# RG_Medium_Matrix.net
KiCad netlist of a schematic drawn in EAGLE
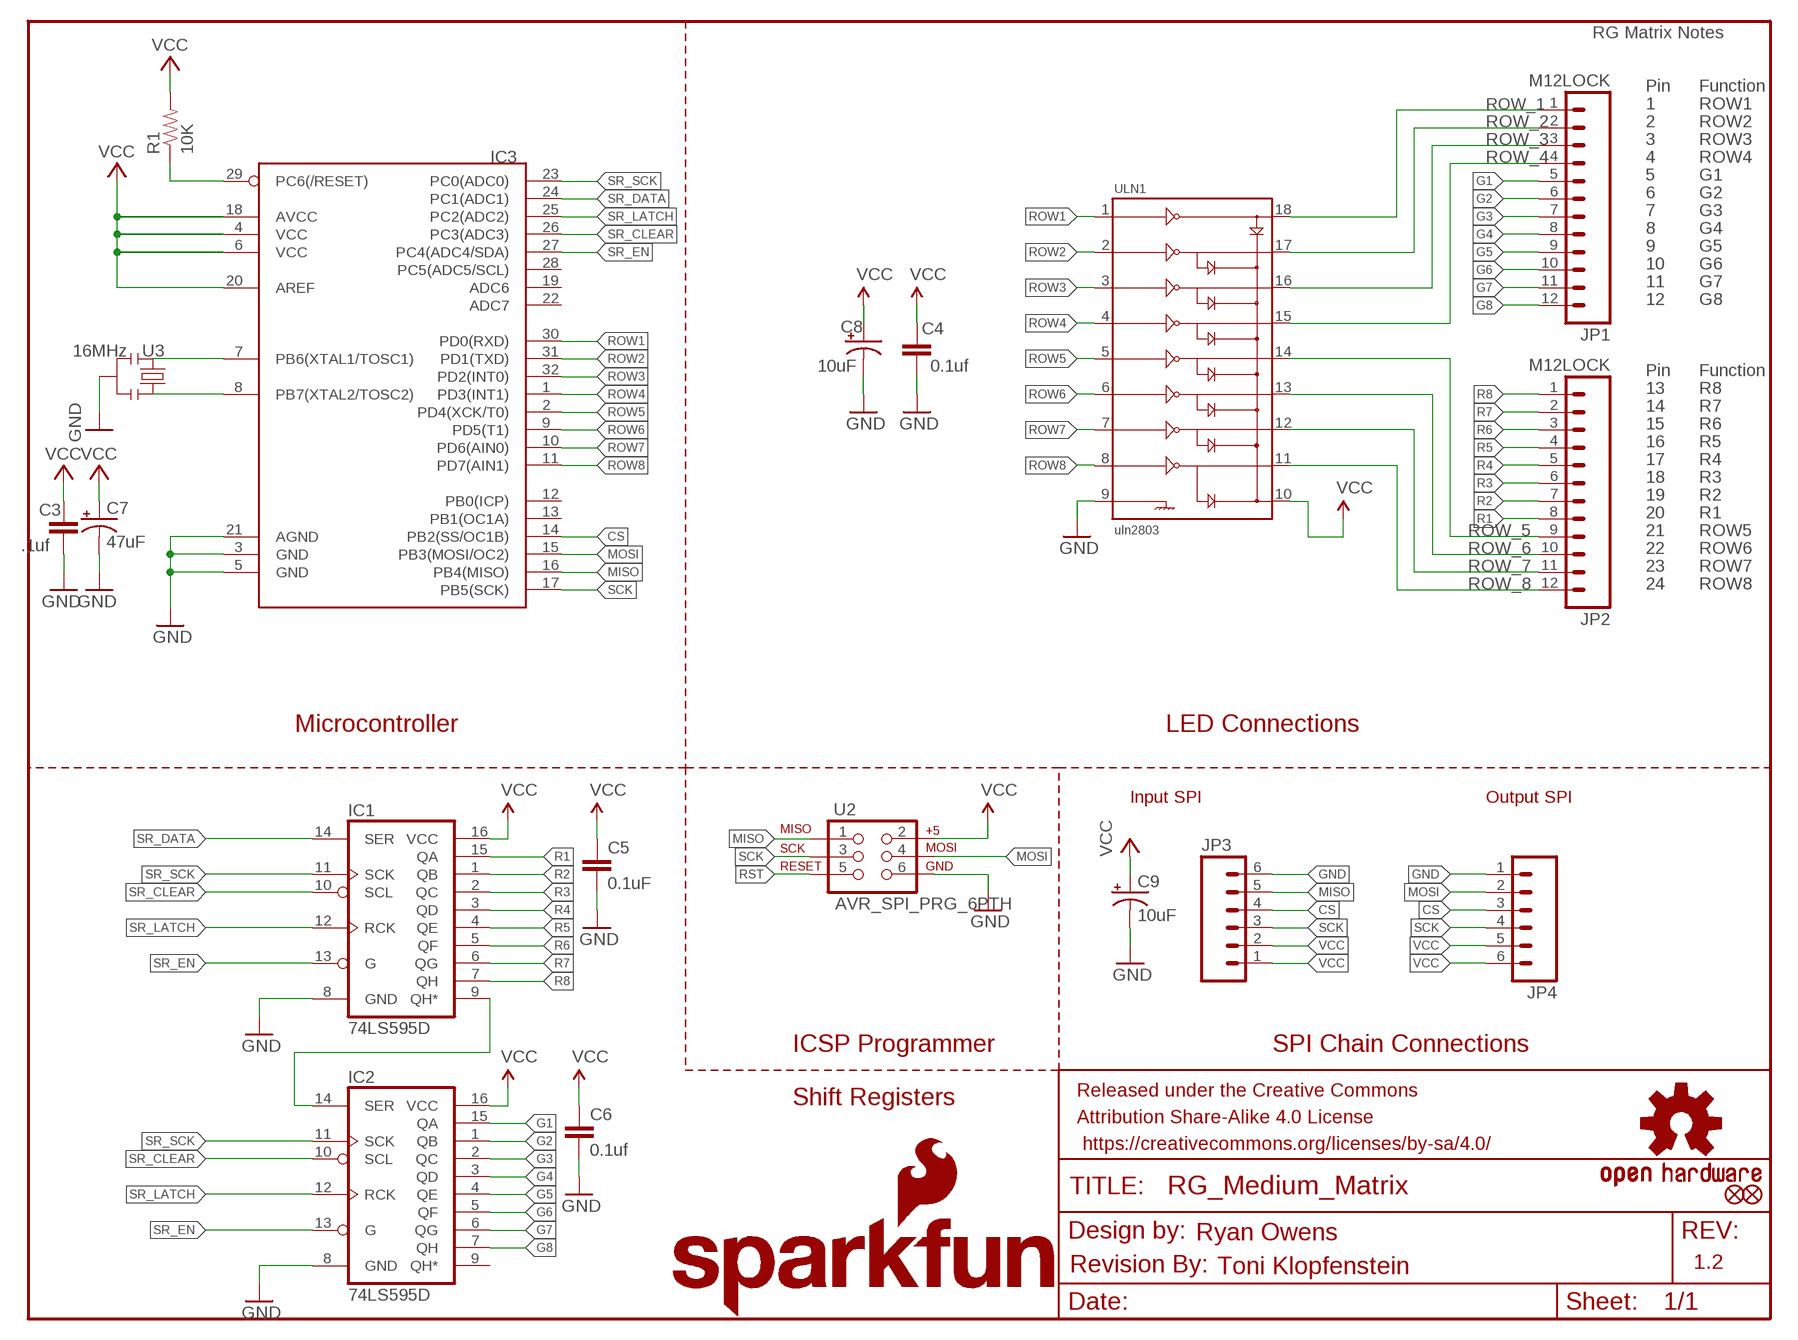
[diagram p0: schematic, sheet 1]

(export (version "E")
  (design (tool "Eeschema 10.0.6"))
  (components
    (comp (ref "C3")
      (value ".1uf")
      (footprint "eagle-import:0603-CAP")
      (libsource (lib "eagle-import") (part "0.1UF-25V(+80/-20%)(0603)"))
    )
    (comp (ref "C4")
      (value "0.1uf")
      (footprint "eagle-import:0603-CAP")
      (libsource (lib "eagle-import") (part "0.1UF-25V(+80/-20%)(0603)"))
    )
    (comp (ref "C5")
      (value "0.1uF")
      (footprint "eagle-import:0603-CAP")
      (libsource (lib "eagle-import") (part "0.1UF-25V(+80/-20%)(0603)"))
    )
    (comp (ref "C6")
      (value "0.1uf")
      (footprint "eagle-import:0603-CAP")
      (libsource (lib "eagle-import") (part "0.1UF-25V(+80/-20%)(0603)"))
    )
    (comp (ref "C7")
      (value "47uF")
      (footprint "eagle-import:EIA3528")
      (libsource (lib "eagle-import") (part "CAP_POL3528"))
    )
    (comp (ref "C8")
      (value "10uF")
      (footprint "eagle-import:EIA3216")
      (libsource (lib "eagle-import") (part "CAP_POL1206"))
    )
    (comp (ref "C9")
      (value "10uF")
      (footprint "eagle-import:EIA3216")
      (libsource (lib "eagle-import") (part "CAP_POL1206"))
    )
    (comp (ref "FRAME1")
      (value "FRAME-LETTER")
      (footprint "eagle-import:CREATIVE_COMMONS")
      (libsource (lib "eagle-import") (part "FRAME-LETTER"))
    )
    (comp (ref "IC1")
      (value "74LS595D")
      (footprint "eagle-import:SO16")
      (libsource (lib "eagle-import") (part "74595DLS"))
    )
    (comp (ref "IC2")
      (value "74LS595D")
      (footprint "eagle-import:SO16")
      (libsource (lib "eagle-import") (part "74595DLS"))
    )
    (comp (ref "IC3")
      (value "ATMEGA328_SMT")
      (footprint "eagle-import:TQFP32-08")
      (libsource (lib "eagle-import") (part "ATMEGA328_SMT"))
    )
    (comp (ref "JP1")
      (value "M12LOCK")
      (footprint "eagle-import:1X12_LOCK")
      (libsource (lib "eagle-import") (part "M12LOCK"))
    )
    (comp (ref "JP2")
      (value "M12LOCK")
      (footprint "eagle-import:1X12_LOCK")
      (libsource (lib "eagle-import") (part "M12LOCK"))
    )
    (comp (ref "JP3")
      (value "M06LOCK")
      (footprint "eagle-import:1X06_LOCK")
      (libsource (lib "eagle-import") (part "M06LOCK"))
    )
    (comp (ref "JP4")
      (value "M06LOCK")
      (footprint "eagle-import:1X06_LOCK")
      (libsource (lib "eagle-import") (part "M06LOCK"))
    )
    (comp (ref "LOGO1")
      (value "OSHW-LOGOS")
      (footprint "eagle-import:OSHW-LOGO-S")
      (libsource (lib "eagle-import") (part "OSHW-LOGOS"))
    )
    (comp (ref "LOGO2")
      (value "SFE_LOGO_NAME_FLAME.1_INCH")
      (footprint "eagle-import:SFE_LOGO_NAME_FLAME_.1")
      (libsource (lib "eagle-import") (part "SFE_LOGO_NAME_FLAME.1_INCH"))
    )
    (comp (ref "R1")
      (value "10K")
      (footprint "eagle-import:0603-RES")
      (libsource (lib "eagle-import") (part "10KOHM1/10W1%(0603)0603"))
    )
    (comp (ref "U$1")
      (value "FIDUCIAL1X2")
      (footprint "eagle-import:FIDUCIAL-1X2")
      (libsource (lib "eagle-import") (part "FIDUCIAL1X2"))
    )
    (comp (ref "U$2")
      (value "REVISION")
      (footprint "eagle-import:REVISION")
      (libsource (lib "eagle-import") (part "REVISION"))
    )
    (comp (ref "U$3")
      (value "FIDUCIAL1X2")
      (footprint "eagle-import:FIDUCIAL-1X2")
      (libsource (lib "eagle-import") (part "FIDUCIAL1X2"))
    )
    (comp (ref "U2")
      (value "AVR_SPI_PRG_6PTH")
      (footprint "eagle-import:2X3")
      (libsource (lib "eagle-import") (part "AVR_SPI_PRG_6PTH"))
    )
    (comp (ref "U3")
      (value "16MHz")
      (footprint "eagle-import:RESONATOR-SMD")
      (libsource (lib "eagle-import") (part "RESONATORSMD"))
    )
    (comp (ref "ULN1")
      (value "uln2803")
      (footprint "eagle-import:SO18L")
      (libsource (lib "eagle-import") (part "ULN2803SOICW"))
    )
  )
  (nets
    (net (code "1") (name "/ROW_1") (class "Default")
      (node (ref "JP1") (pin "1") (pinfunction "1_1") (pintype "passive"))
      (node (ref "ULN1") (pin "18") (pinfunction "18_18") (pintype "bidirectional"))
    )
    (net (code "2") (name "/ROW_2") (class "Default")
      (node (ref "JP1") (pin "2") (pinfunction "2_2") (pintype "passive"))
      (node (ref "ULN1") (pin "17") (pinfunction "17_17") (pintype "bidirectional"))
    )
    (net (code "3") (name "/ROW_3") (class "Default")
      (node (ref "JP1") (pin "3") (pinfunction "3_3") (pintype "passive"))
      (node (ref "ULN1") (pin "16") (pinfunction "16_16") (pintype "bidirectional"))
    )
    (net (code "4") (name "/ROW_4") (class "Default")
      (node (ref "JP1") (pin "4") (pinfunction "4_4") (pintype "passive"))
      (node (ref "ULN1") (pin "15") (pinfunction "15_15") (pintype "bidirectional"))
    )
    (net (code "5") (name "/ROW_5") (class "Default")
      (node (ref "JP2") (pin "9") (pinfunction "9_9") (pintype "passive"))
      (node (ref "ULN1") (pin "14") (pinfunction "14_14") (pintype "bidirectional"))
    )
    (net (code "6") (name "/ROW_6") (class "Default")
      (node (ref "JP2") (pin "10") (pinfunction "10_10") (pintype "passive"))
      (node (ref "ULN1") (pin "13") (pinfunction "13_13") (pintype "bidirectional"))
    )
    (net (code "7") (name "/ROW_7") (class "Default")
      (node (ref "JP2") (pin "11") (pinfunction "11_11") (pintype "passive"))
      (node (ref "ULN1") (pin "12") (pinfunction "12_12") (pintype "bidirectional"))
    )
    (net (code "8") (name "/ROW_8") (class "Default")
      (node (ref "JP2") (pin "12") (pinfunction "12_12") (pintype "passive"))
      (node (ref "ULN1") (pin "11") (pinfunction "11_11") (pintype "bidirectional"))
    )
    (net (code "9") (name "CS") (class "Default")
      (node (ref "IC3") (pin "14") (pinfunction "PB2(SS/OC1B)_14") (pintype "bidirectional"))
      (node (ref "JP3") (pin "4") (pinfunction "4_4") (pintype "passive"))
      (node (ref "JP4") (pin "3") (pinfunction "3_3") (pintype "passive"))
    )
    (net (code "10") (name "G1") (class "Default")
      (node (ref "IC2") (pin "15") (pinfunction "QA_15") (pintype "tri_state"))
      (node (ref "JP1") (pin "5") (pinfunction "5_5") (pintype "passive"))
    )
    (net (code "11") (name "G2") (class "Default")
      (node (ref "IC2") (pin "1") (pinfunction "QB_1") (pintype "tri_state"))
      (node (ref "JP1") (pin "6") (pinfunction "6_6") (pintype "passive"))
    )
    (net (code "12") (name "G3") (class "Default")
      (node (ref "IC2") (pin "2") (pinfunction "QC_2") (pintype "tri_state"))
      (node (ref "JP1") (pin "7") (pinfunction "7_7") (pintype "passive"))
    )
    (net (code "13") (name "G4") (class "Default")
      (node (ref "IC2") (pin "3") (pinfunction "QD_3") (pintype "tri_state"))
      (node (ref "JP1") (pin "8") (pinfunction "8_8") (pintype "passive"))
    )
    (net (code "14") (name "G5") (class "Default")
      (node (ref "IC2") (pin "4") (pinfunction "QE_4") (pintype "tri_state"))
      (node (ref "JP1") (pin "9") (pinfunction "9_9") (pintype "passive"))
    )
    (net (code "15") (name "G6") (class "Default")
      (node (ref "IC2") (pin "5") (pinfunction "QF_5") (pintype "tri_state"))
      (node (ref "JP1") (pin "10") (pinfunction "10_10") (pintype "passive"))
    )
    (net (code "16") (name "G7") (class "Default")
      (node (ref "IC2") (pin "6") (pinfunction "QG_6") (pintype "tri_state"))
      (node (ref "JP1") (pin "11") (pinfunction "11_11") (pintype "passive"))
    )
    (net (code "17") (name "G8") (class "Default")
      (node (ref "IC2") (pin "7") (pinfunction "QH_7") (pintype "tri_state"))
      (node (ref "JP1") (pin "12") (pinfunction "12_12") (pintype "passive"))
    )
    (net (code "18") (name "GND") (class "Default")
      (node (ref "C3") (pin "2") (pinfunction "2_2") (pintype "passive"))
      (node (ref "C4") (pin "1") (pinfunction "1_1") (pintype "passive"))
      (node (ref "C5") (pin "2") (pinfunction "2_2") (pintype "passive"))
      (node (ref "C6") (pin "2") (pinfunction "2_2") (pintype "passive"))
      (node (ref "C7") (pin "C") (pinfunction "-_C") (pintype "passive"))
      (node (ref "C8") (pin "C") (pinfunction "-_C") (pintype "passive"))
      (node (ref "C9") (pin "C") (pinfunction "-_C") (pintype "passive"))
      (node (ref "IC1") (pin "8") (pinfunction "GND_8") (pintype "power_in"))
      (node (ref "IC2") (pin "8") (pinfunction "GND_8") (pintype "power_in"))
      (node (ref "IC3") (pin "21") (pinfunction "AGND_21") (pintype "bidirectional"))
      (node (ref "IC3") (pin "3") (pinfunction "GND_3") (pintype "bidirectional"))
      (node (ref "IC3") (pin "5") (pinfunction "GND_5") (pintype "bidirectional"))
      (node (ref "JP3") (pin "6") (pinfunction "6_6") (pintype "passive"))
      (node (ref "JP4") (pin "1") (pinfunction "1_1") (pintype "passive"))
      (node (ref "U2") (pin "6") (pinfunction "6_6") (pintype "passive"))
      (node (ref "U3") (pin "2") (pinfunction "2_2") (pintype "passive"))
      (node (ref "ULN1") (pin "9") (pinfunction "9_9") (pintype "bidirectional"))
    )
    (net (code "19") (name "MISO") (class "Default")
      (node (ref "IC3") (pin "16") (pinfunction "PB4(MISO)_16") (pintype "bidirectional"))
      (node (ref "JP3") (pin "5") (pinfunction "5_5") (pintype "passive"))
      (node (ref "U2") (pin "1") (pinfunction "1_1") (pintype "passive"))
    )
    (net (code "20") (name "MOSI") (class "Default")
      (node (ref "IC3") (pin "15") (pinfunction "PB3(MOSI/OC2)_15") (pintype "bidirectional"))
      (node (ref "JP4") (pin "2") (pinfunction "2_2") (pintype "passive"))
      (node (ref "U2") (pin "4") (pinfunction "4_4") (pintype "passive"))
    )
    (net (code "21") (name "Net-(IC1-QH*)") (class "Default")
      (node (ref "IC1") (pin "9") (pinfunction "QH*_9") (pintype "tri_state"))
      (node (ref "IC2") (pin "14") (pinfunction "SER_14") (pintype "input"))
    )
    (net (code "22") (name "Net-(IC3-PB6(XTAL1{slash}TOSC1))") (class "Default")
      (node (ref "IC3") (pin "7") (pinfunction "PB6(XTAL1/TOSC1)_7") (pintype "bidirectional"))
      (node (ref "U3") (pin "1") (pinfunction "1_1") (pintype "passive"))
    )
    (net (code "23") (name "Net-(IC3-PB7(XTAL2{slash}TOSC2))") (class "Default")
      (node (ref "IC3") (pin "8") (pinfunction "PB7(XTAL2/TOSC2)_8") (pintype "bidirectional"))
      (node (ref "U3") (pin "3") (pinfunction "3_3") (pintype "passive"))
    )
    (net (code "24") (name "R1") (class "Default")
      (node (ref "IC1") (pin "15") (pinfunction "QA_15") (pintype "tri_state"))
      (node (ref "JP2") (pin "8") (pinfunction "8_8") (pintype "passive"))
    )
    (net (code "25") (name "R2") (class "Default")
      (node (ref "IC1") (pin "1") (pinfunction "QB_1") (pintype "tri_state"))
      (node (ref "JP2") (pin "7") (pinfunction "7_7") (pintype "passive"))
    )
    (net (code "26") (name "R3") (class "Default")
      (node (ref "IC1") (pin "2") (pinfunction "QC_2") (pintype "tri_state"))
      (node (ref "JP2") (pin "6") (pinfunction "6_6") (pintype "passive"))
    )
    (net (code "27") (name "R4") (class "Default")
      (node (ref "IC1") (pin "3") (pinfunction "QD_3") (pintype "tri_state"))
      (node (ref "JP2") (pin "5") (pinfunction "5_5") (pintype "passive"))
    )
    (net (code "28") (name "R5") (class "Default")
      (node (ref "IC1") (pin "4") (pinfunction "QE_4") (pintype "tri_state"))
      (node (ref "JP2") (pin "4") (pinfunction "4_4") (pintype "passive"))
    )
    (net (code "29") (name "R6") (class "Default")
      (node (ref "IC1") (pin "5") (pinfunction "QF_5") (pintype "tri_state"))
      (node (ref "JP2") (pin "3") (pinfunction "3_3") (pintype "passive"))
    )
    (net (code "30") (name "R7") (class "Default")
      (node (ref "IC1") (pin "6") (pinfunction "QG_6") (pintype "tri_state"))
      (node (ref "JP2") (pin "2") (pinfunction "2_2") (pintype "passive"))
    )
    (net (code "31") (name "R8") (class "Default")
      (node (ref "IC1") (pin "7") (pinfunction "QH_7") (pintype "tri_state"))
      (node (ref "JP2") (pin "1") (pinfunction "1_1") (pintype "passive"))
    )
    (net (code "32") (name "ROW1") (class "Default")
      (node (ref "IC3") (pin "30") (pinfunction "PD0(RXD)_30") (pintype "bidirectional"))
      (node (ref "ULN1") (pin "1") (pinfunction "1_1") (pintype "bidirectional"))
    )
    (net (code "33") (name "ROW2") (class "Default")
      (node (ref "IC3") (pin "31") (pinfunction "PD1(TXD)_31") (pintype "bidirectional"))
      (node (ref "ULN1") (pin "2") (pinfunction "2_2") (pintype "bidirectional"))
    )
    (net (code "34") (name "ROW3") (class "Default")
      (node (ref "IC3") (pin "32") (pinfunction "PD2(INT0)_32") (pintype "bidirectional"))
      (node (ref "ULN1") (pin "3") (pinfunction "3_3") (pintype "bidirectional"))
    )
    (net (code "35") (name "ROW4") (class "Default")
      (node (ref "IC3") (pin "1") (pinfunction "PD3(INT1)_1") (pintype "bidirectional"))
      (node (ref "ULN1") (pin "4") (pinfunction "4_4") (pintype "bidirectional"))
    )
    (net (code "36") (name "ROW5") (class "Default")
      (node (ref "IC3") (pin "2") (pinfunction "PD4(XCK/T0)_2") (pintype "bidirectional"))
      (node (ref "ULN1") (pin "5") (pinfunction "5_5") (pintype "bidirectional"))
    )
    (net (code "37") (name "ROW6") (class "Default")
      (node (ref "IC3") (pin "9") (pinfunction "PD5(T1)_9") (pintype "bidirectional"))
      (node (ref "ULN1") (pin "6") (pinfunction "6_6") (pintype "bidirectional"))
    )
    (net (code "38") (name "ROW7") (class "Default")
      (node (ref "IC3") (pin "10") (pinfunction "PD6(AIN0)_10") (pintype "bidirectional"))
      (node (ref "ULN1") (pin "7") (pinfunction "7_7") (pintype "bidirectional"))
    )
    (net (code "39") (name "ROW8") (class "Default")
      (node (ref "IC3") (pin "11") (pinfunction "PD7(AIN1)_11") (pintype "bidirectional"))
      (node (ref "ULN1") (pin "8") (pinfunction "8_8") (pintype "bidirectional"))
    )
    (net (code "40") (name "RST") (class "Default")
      (node (ref "IC3") (pin "29") (pinfunction "PC6(/RESET)_29") (pintype "bidirectional"))
      (node (ref "R1") (pin "1") (pinfunction "1_1") (pintype "passive"))
      (node (ref "U2") (pin "5") (pinfunction "5_5") (pintype "passive"))
    )
    (net (code "41") (name "SCK") (class "Default")
      (node (ref "IC3") (pin "17") (pinfunction "PB5(SCK)_17") (pintype "bidirectional"))
      (node (ref "JP3") (pin "3") (pinfunction "3_3") (pintype "passive"))
      (node (ref "JP4") (pin "4") (pinfunction "4_4") (pintype "passive"))
      (node (ref "U2") (pin "3") (pinfunction "3_3") (pintype "passive"))
    )
    (net (code "42") (name "SR_CLEAR") (class "Default")
      (node (ref "IC1") (pin "10") (pinfunction "SCL_10") (pintype "input"))
      (node (ref "IC2") (pin "10") (pinfunction "SCL_10") (pintype "input"))
      (node (ref "IC3") (pin "26") (pinfunction "PC3(ADC3)_26") (pintype "bidirectional"))
    )
    (net (code "43") (name "SR_DATA") (class "Default")
      (node (ref "IC1") (pin "14") (pinfunction "SER_14") (pintype "input"))
      (node (ref "IC3") (pin "24") (pinfunction "PC1(ADC1)_24") (pintype "bidirectional"))
    )
    (net (code "44") (name "SR_EN") (class "Default")
      (node (ref "IC1") (pin "13") (pinfunction "G_13") (pintype "input"))
      (node (ref "IC2") (pin "13") (pinfunction "G_13") (pintype "input"))
      (node (ref "IC3") (pin "27") (pinfunction "PC4(ADC4/SDA)_27") (pintype "bidirectional"))
    )
    (net (code "45") (name "SR_LATCH") (class "Default")
      (node (ref "IC1") (pin "12") (pinfunction "RCK_12") (pintype "input"))
      (node (ref "IC2") (pin "12") (pinfunction "RCK_12") (pintype "input"))
      (node (ref "IC3") (pin "25") (pinfunction "PC2(ADC2)_25") (pintype "bidirectional"))
    )
    (net (code "46") (name "SR_SCK") (class "Default")
      (node (ref "IC1") (pin "11") (pinfunction "SCK_11") (pintype "input"))
      (node (ref "IC2") (pin "11") (pinfunction "SCK_11") (pintype "input"))
      (node (ref "IC3") (pin "23") (pinfunction "PC0(ADC0)_23") (pintype "bidirectional"))
    )
    (net (code "47") (name "VCC") (class "Default")
      (node (ref "C3") (pin "1") (pinfunction "1_1") (pintype "passive"))
      (node (ref "C4") (pin "2") (pinfunction "2_2") (pintype "passive"))
      (node (ref "C5") (pin "1") (pinfunction "1_1") (pintype "passive"))
      (node (ref "C6") (pin "1") (pinfunction "1_1") (pintype "passive"))
      (node (ref "C7") (pin "A") (pinfunction "+_A") (pintype "passive"))
      (node (ref "C8") (pin "A") (pinfunction "+_A") (pintype "passive"))
      (node (ref "C9") (pin "A") (pinfunction "+_A") (pintype "passive"))
      (node (ref "IC1") (pin "16") (pinfunction "VCC_16") (pintype "power_in"))
      (node (ref "IC2") (pin "16") (pinfunction "VCC_16") (pintype "power_in"))
      (node (ref "IC3") (pin "18") (pinfunction "AVCC_18") (pintype "bidirectional"))
      (node (ref "IC3") (pin "20") (pinfunction "AREF_20") (pintype "bidirectional"))
      (node (ref "IC3") (pin "4") (pinfunction "VCC_4") (pintype "bidirectional"))
      (node (ref "IC3") (pin "6") (pinfunction "VCC_6") (pintype "bidirectional"))
      (node (ref "JP3") (pin "1") (pinfunction "1_1") (pintype "passive"))
      (node (ref "JP3") (pin "2") (pinfunction "2_2") (pintype "passive"))
      (node (ref "JP4") (pin "5") (pinfunction "5_5") (pintype "passive"))
      (node (ref "JP4") (pin "6") (pinfunction "6_6") (pintype "passive"))
      (node (ref "R1") (pin "2") (pinfunction "2_2") (pintype "passive"))
      (node (ref "U2") (pin "2") (pinfunction "2_2") (pintype "passive"))
      (node (ref "ULN1") (pin "10") (pinfunction "10_10") (pintype "bidirectional"))
    )
    (net (code "48") (name "unconnected-(IC2-QH*-Pad9)") (class "Default")
      (node (ref "IC2") (pin "9") (pinfunction "QH*_9") (pintype "tri_state"))
    )
    (net (code "49") (name "unconnected-(IC3-ADC6-Pad19)") (class "Default")
      (node (ref "IC3") (pin "19") (pinfunction "ADC6_19") (pintype "bidirectional"))
    )
    (net (code "50") (name "unconnected-(IC3-ADC7-Pad22)") (class "Default")
      (node (ref "IC3") (pin "22") (pinfunction "ADC7_22") (pintype "bidirectional"))
    )
    (net (code "51") (name "unconnected-(IC3-PB0(ICP)-Pad12)") (class "Default")
      (node (ref "IC3") (pin "12") (pinfunction "PB0(ICP)_12") (pintype "bidirectional"))
    )
    (net (code "52") (name "unconnected-(IC3-PB1(OC1A)-Pad13)") (class "Default")
      (node (ref "IC3") (pin "13") (pinfunction "PB1(OC1A)_13") (pintype "bidirectional"))
    )
    (net (code "53") (name "unconnected-(IC3-PC5(ADC5{slash}SCL)-Pad28)") (class "Default")
      (node (ref "IC3") (pin "28") (pinfunction "PC5(ADC5/SCL)_28") (pintype "bidirectional"))
    )
  )
)
